# P06_PLP.net
KiCad netlist of a schematic drawn in Altium Designer
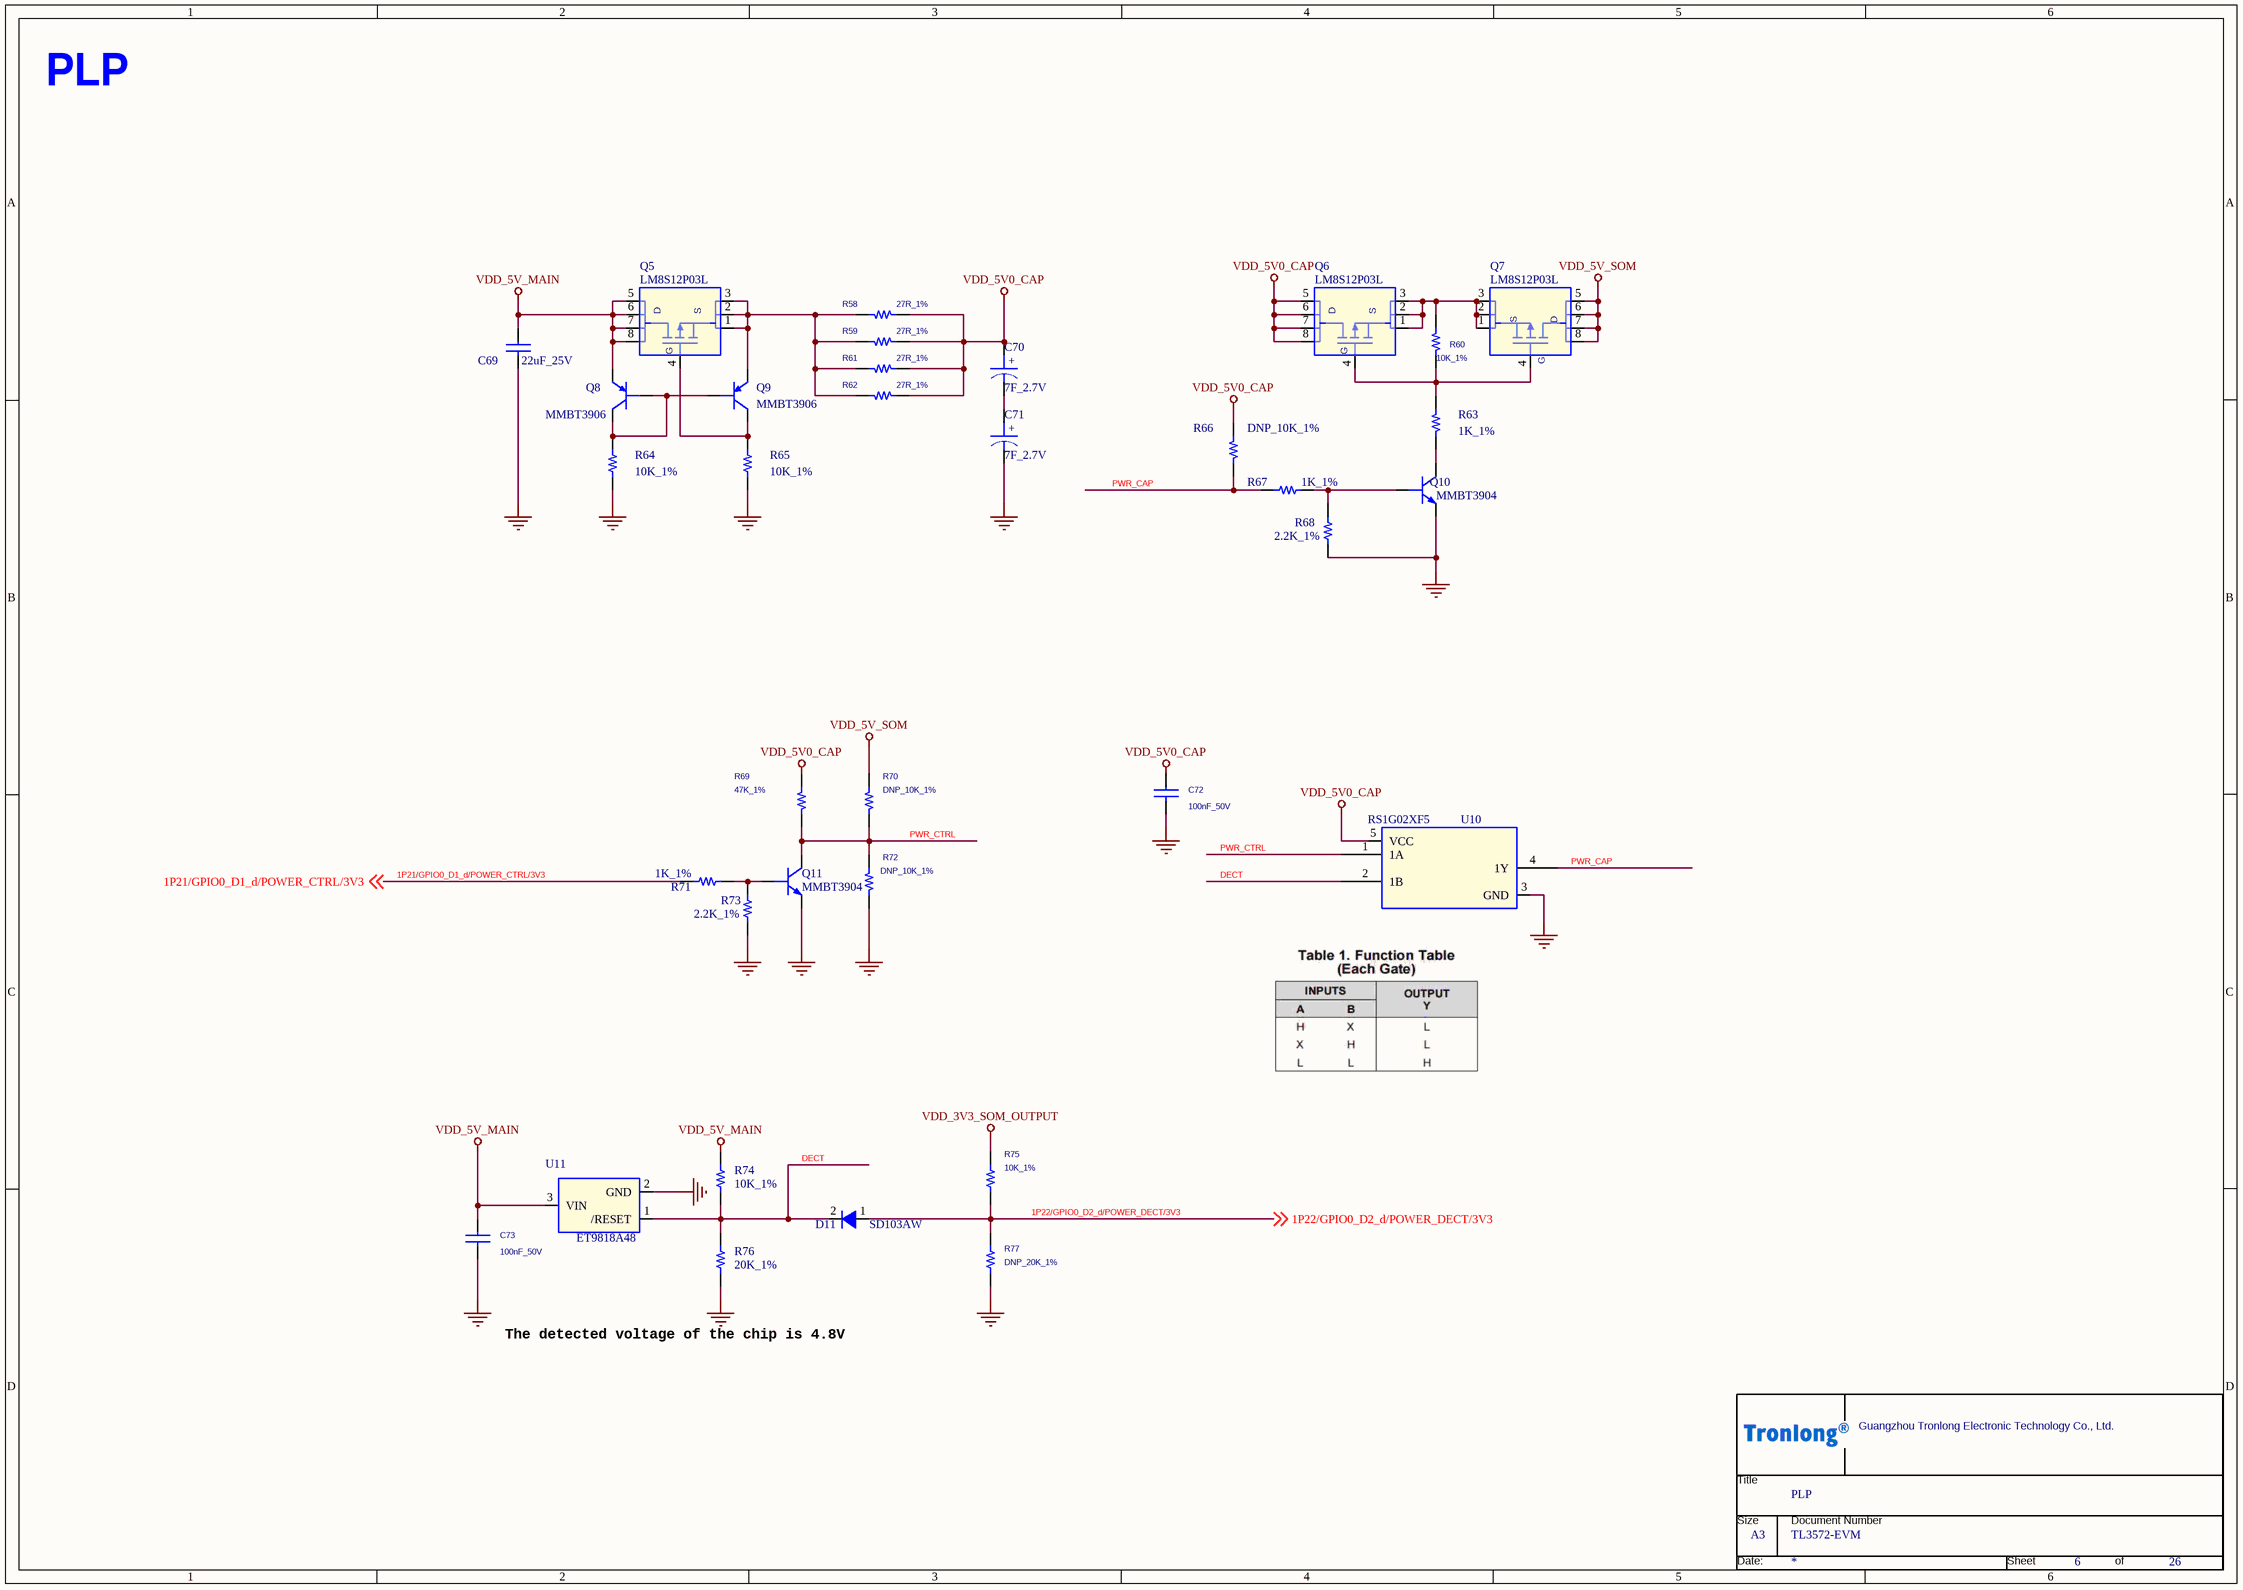
[diagram p0: P06_PLP.SchDoc]

(export (version "E")
  (design (tool "Eeschema 10.0.6"))
  (components
    (comp (ref "*")
      (value "TL_NEW")
      (fields
        (field (name "PAGE COUNT") "26")
        (field (name "PAGE NUMBER") "6")
        (field (name "PAGE SIZE") "A3")
        (field (name "ORGNAME") "Guangzhou Tronlong Electronic Technology Co., Ltd.")
        (field (name "TITLE") "PLP")
        (field (name "DOC") "TL3572-EVM")
      )
      (libsource (lib "*") (part "TL_NEW"))
    )
    (comp (ref "C69")
      (value "22uF_25V")
      (footprint "C0805")
      (description "贴片陶瓷电容,22uF,20%,25V,X5R")
      (fields
        (field (name "MANUFACTURER") "广东风华高新科技股份有限公司（FH）")
        (field (name "MANUFACTURER PARTNUMBER") "0805X226M250NT")
      )
      (libsource (lib "*") (part "CAP NP_Dup2"))
    )
    (comp (ref "C70")
      (value "7F_2.7V")
      (footprint "dcc3-5_0-10_5x20_5_0-down")
      (description "超级电容,7F,2.7V,卧式")
      (fields
        (field (name "MANUFACTURER PARTNUMBER") "HT-2R7-J705UYJ13(G211）")
        (field (name "MANUFACTURER") "锦州凯美能源有限公司（KAMCAP）")
      )
      (libsource (lib "*") (part "CAP POL_Dup1"))
    )
    (comp (ref "C71")
      (value "7F_2.7V")
      (footprint "dcc3-5_0-10_5x20_5_0-down")
      (description "超级电容,7F,2.7V,卧式")
      (fields
        (field (name "MANUFACTURER PARTNUMBER") "HT-2R7-J705UYJ13(G211）")
        (field (name "MANUFACTURER") "锦州凯美能源有限公司（KAMCAP）")
      )
      (libsource (lib "*") (part "CAP POL_Dup1"))
    )
    (comp (ref "C72")
      (value "100nF_50V")
      (footprint "C0402")
      (description "贴片陶瓷电容,100nF,10%,50V,X7R")
      (fields
        (field (name "MANUFACTURER PARTNUMBER") "0402B104K500NT")
        (field (name "MANUFACTURER") "广东风华高新科技股份有限公司（FH）")
      )
      (libsource (lib "*") (part "CAP_NP_Dup1"))
    )
    (comp (ref "C73")
      (value "100nF_50V")
      (footprint "C0402")
      (description "贴片陶瓷电容,100nF,10%,50V,X7R")
      (fields
        (field (name "MANUFACTURER PARTNUMBER") "0402B104K500NT")
        (field (name "MANUFACTURER") "广东风华高新科技股份有限公司（FH）")
      )
      (libsource (lib "*") (part "CAP_NP_Dup1"))
    )
    (comp (ref "D11")
      (value "SD103AW")
      (footprint "SOD-123_NEW")
      (description "肖特基二极管,VR=40V,IF=350mA,VF=0.37V@20mA,trr=10ns")
      (fields (field (name "TIINTPARTNUMBER") "1E0013") (field (name "MFR") "On Semiconductor"))
      (libsource (lib "*") (part "Diode200mA250V_1"))
    )
    (comp (ref "Q5")
      (value "LM8S12P03L")
      (footprint "PSOPSOP-8L")
      (description "MOSFET,P沟道,VDSS=-30V,VGSS=±20V,ID=-12A,PD=3.1W,VGS(th)=-1.5V")
      (fields (field (name "MANUFACTURER") "上海雷卯电子科技有限公司（Leiditech）"))
      (libsource (lib "") (part "WPM3021_1"))
    )
    (comp (ref "Q6")
      (value "LM8S12P03L")
      (footprint "PSOPSOP-8L")
      (description "MOSFET,P沟道,VDSS=-30V,VGSS=±20V,ID=-12A,PD=3.1W,VGS(th)=-1.5V")
      (fields (field (name "MANUFACTURER") "上海雷卯电子科技有限公司（Leiditech）"))
      (libsource (lib "") (part "WPM3021_1"))
    )
    (comp (ref "Q7")
      (value "LM8S12P03L")
      (footprint "PSOPSOP-8L")
      (description "MOSFET,P沟道,VDSS=-30V,VGSS=±20V,ID=-12A,PD=3.1W,VGS(th)=-1.5V")
      (fields (field (name "MANUFACTURER") "上海雷卯电子科技有限公司（Leiditech）"))
      (libsource (lib "*") (part "WPM3021"))
    )
    (comp (ref "Q8")
      (value "MMBT3906")
      (footprint "SOT23-3_DBZ3")
      (description "BJT,PNP,Vceo=-40V,Ic=-200mA,fT=300MHz,PD=200mW")
      (fields (field (name "MANUFACTURER") "江苏长晶科技股份有限公司（JSCJ）"))
      (libsource (lib "*") (part "MMBT3904/SOT_0"))
    )
    (comp (ref "Q9")
      (value "MMBT3906")
      (footprint "SOT23-3_DBZ3")
      (description "BJT,PNP,Vceo=-40V,Ic=-200mA,fT=300MHz,PD=200mW")
      (fields (field (name "MANUFACTURER") "江苏长晶科技股份有限公司（JSCJ）"))
      (libsource (lib "*") (part "MMBT3904/SOT_0"))
    )
    (comp (ref "Q10")
      (value "MMBT3904")
      (footprint "SOT23-3_DBZ3")
      (description "BJT,NPN,Vceo=40V,Ic=200mA,fT=300MHz,PD=200mW")
      (fields (field (name "MANUFACTURER") "江苏长晶科技股份有限公司（JSCJ）"))
      (libsource (lib "*") (part "MMBT3904/SOT"))
    )
    (comp (ref "Q11")
      (value "MMBT3904")
      (footprint "SOT23-3_DBZ3")
      (description "BJT,NPN,Vceo=40V,Ic=200mA,fT=300MHz,PD=200mW")
      (fields (field (name "MANUFACTURER") "江苏长晶科技股份有限公司（JSCJ）"))
      (libsource (lib "*") (part "MMBT3904/SOT"))
    )
    (comp (ref "R58")
      (value "27R_1%")
      (footprint "R2512")
      (description "25121WF270JT4E")
      (fields
        (field (name "MANUFACTURER") "广州创龙")
        (field (name "MANUFACTURER PARTNUMBER") "27R,±1%,R2512,≥1W")
      )
      (libsource (lib "*") (part "Resistor_Dup3"))
    )
    (comp (ref "R59")
      (value "27R_1%")
      (footprint "R2512")
      (description "25121WF270JT4E")
      (fields
        (field (name "MANUFACTURER") "广州创龙")
        (field (name "MANUFACTURER PARTNUMBER") "27R,±1%,R2512,≥1W")
      )
      (libsource (lib "*") (part "Resistor_Dup3"))
    )
    (comp (ref "R60")
      (value "10K_1%")
      (footprint "R0402")
      (description "贴片电阻,10K,±1%,1/16W")
      (fields
        (field (name "MANUFACTURER") "广东风华高新科技股份有限公司（FH）")
        (field (name "MANUFACTURER PARTNUMBER") "RC-02K1002FT")
      )
      (libsource (lib "*") (part "Resistor_Dup3"))
    )
    (comp (ref "R61")
      (value "27R_1%")
      (footprint "R2512")
      (description "25121WF270JT4E")
      (fields
        (field (name "MANUFACTURER") "广州创龙")
        (field (name "MANUFACTURER PARTNUMBER") "27R,±1%,R2512,≥1W")
      )
      (libsource (lib "*") (part "Resistor_Dup3"))
    )
    (comp (ref "R62")
      (value "27R_1%")
      (footprint "R2512")
      (description "25121WF270JT4E")
      (fields
        (field (name "MANUFACTURER") "广州创龙")
        (field (name "MANUFACTURER PARTNUMBER") "27R,±1%,R2512,≥1W")
      )
      (libsource (lib "*") (part "Resistor_Dup3"))
    )
    (comp (ref "R63")
      (value "1K_1%")
      (footprint "R0402")
      (description "贴片电阻,1K,±1%,1/16W")
      (fields
        (field (name "MANUFACTURER PARTNUMBER") "RC-02K1001FT")
        (field (name "MANUFACTURER") "广东风华高新科技股份有限公司（FH）")
      )
      (libsource (lib "*") (part "Resistor_Dup3"))
    )
    (comp (ref "R64")
      (value "10K_1%")
      (footprint "R0402")
      (description "贴片电阻,10K,±1%,1/16W")
      (fields
        (field (name "MANUFACTURER PARTNUMBER") "RC-02K1002FT")
        (field (name "MANUFACTURER") "广东风华高新科技股份有限公司（FH）")
      )
      (libsource (lib "*") (part "Resistor_Dup3"))
    )
    (comp (ref "R65")
      (value "10K_1%")
      (footprint "R0402")
      (description "贴片电阻,10K,±1%,1/16W")
      (fields
        (field (name "MANUFACTURER") "广东风华高新科技股份有限公司（FH）")
        (field (name "MANUFACTURER PARTNUMBER") "RC-02K1002FT")
      )
      (libsource (lib "*") (part "Resistor_Dup3"))
    )
    (comp (ref "R66")
      (value "DNP_10K_1%")
      (footprint "R0402")
      (description "贴片电阻,10K,±1%,1/16W")
      (fields
        (field (name "MANUFACTURER") "广东风华高新科技股份有限公司（FH）")
        (field (name "MANUFACTURER PARTNUMBER") "RC-02K1002FT")
      )
      (libsource (lib "*") (part "Resistor_Dup3"))
    )
    (comp (ref "R67")
      (value "1K_1%")
      (footprint "R0402")
      (description "贴片电阻,1K,±1%,1/16W")
      (fields
        (field (name "MANUFACTURER") "广东风华高新科技股份有限公司（FH）")
        (field (name "MANUFACTURER PARTNUMBER") "RC-02K1001FT")
      )
      (libsource (lib "*") (part "Resistor_Dup3"))
    )
    (comp (ref "R68")
      (value "2.2K_1%")
      (footprint "R0402")
      (description "贴片电阻,2.2K,±1%,1/16W")
      (fields
        (field (name "MANUFACTURER PARTNUMBER") "RC-02K2201FT")
        (field (name "MANUFACTURER") "广东风华高新科技股份有限公司（FH）")
      )
      (libsource (lib "*") (part "Resistor_Dup3"))
    )
    (comp (ref "R69")
      (value "47K_1%")
      (footprint "R0402")
      (description "贴片电阻,47K,±1%,1/16W")
      (fields
        (field (name "MANUFACTURER") "广东风华高新科技股份有限公司（FH）")
        (field (name "MANUFACTURER PARTNUMBER") "RC-02K4702FT")
      )
      (libsource (lib "*") (part "Resistor_Dup3"))
    )
    (comp (ref "R70")
      (value "DNP_10K_1%")
      (footprint "R0402")
      (description "贴片电阻,10K,±1%,1/16W")
      (fields
        (field (name "MANUFACTURER PARTNUMBER") "RC-02K1002FT")
        (field (name "MANUFACTURER") "广东风华高新科技股份有限公司（FH）")
      )
      (libsource (lib "*") (part "Resistor_Dup3"))
    )
    (comp (ref "R71")
      (value "1K_1%")
      (footprint "R0402")
      (description "贴片电阻,1K,±1%,1/16W")
      (fields
        (field (name "MANUFACTURER") "广东风华高新科技股份有限公司（FH）")
        (field (name "MANUFACTURER PARTNUMBER") "RC-02K1001FT")
      )
      (libsource (lib "*") (part "Resistor_Dup3"))
    )
    (comp (ref "R72")
      (value "DNP_10K_1%")
      (footprint "R0402")
      (description "贴片电阻,10K,±1%,1/16W")
      (fields
        (field (name "MANUFACTURER") "广东风华高新科技股份有限公司（FH）")
        (field (name "MANUFACTURER PARTNUMBER") "RC-02K1002FT")
      )
      (libsource (lib "*") (part "Resistor_Dup3"))
    )
    (comp (ref "R73")
      (value "2.2K_1%")
      (footprint "R0402")
      (description "贴片电阻,2.2K,±1%,1/16W")
      (fields
        (field (name "MANUFACTURER") "广东风华高新科技股份有限公司（FH）")
        (field (name "MANUFACTURER PARTNUMBER") "RC-02K2201FT")
      )
      (libsource (lib "*") (part "Resistor_Dup3"))
    )
    (comp (ref "R74")
      (value "10K_1%")
      (footprint "R0402")
      (description "贴片电阻,10K,±1%,1/16W")
      (fields
        (field (name "MANUFACTURER") "广东风华高新科技股份有限公司（FH）")
        (field (name "MANUFACTURER PARTNUMBER") "RC-02K1002FT")
      )
      (libsource (lib "*") (part "Resistor_Dup3"))
    )
    (comp (ref "R75")
      (value "10K_1%")
      (footprint "R0402")
      (description "贴片电阻,10K,±1%,1/16W")
      (fields
        (field (name "MANUFACTURER PARTNUMBER") "RC-02K1002FT")
        (field (name "MANUFACTURER") "广东风华高新科技股份有限公司（FH）")
      )
      (libsource (lib "*") (part "Resistor_Dup3"))
    )
    (comp (ref "R76")
      (value "20K_1%")
      (footprint "R0603")
      (description "贴片电阻,20K,±1%,1/10W")
      (fields
        (field (name "MANUFACTURER PARTNUMBER") "RS-03K2002FT")
        (field (name "MANUFACTURER") "广东风华高新科技股份有限公司（FH）")
      )
      (libsource (lib "*") (part "Resistor_Dup3"))
    )
    (comp (ref "R77")
      (value "DNP_20K_1%")
      (footprint "R0402")
      (description "贴片电阻,20K,±1%,1/16W")
      (fields
        (field (name "MANUFACTURER") "广东风华高新科技股份有限公司（FH）")
        (field (name "MANUFACTURER PARTNUMBER") "RC-02K2002FT")
      )
      (libsource (lib "*") (part "Resistor_Dup3"))
    )
    (comp (ref "U10")
      (value "RS1G02XF5")
      (footprint "SOT23-5")
      (description "1个两输入或非门")
      (fields (field (name "MANUFACTURER") "江苏润石科技有限公司（RUNIC）"))
      (libsource (lib "TL3572-EVM-A1.0-000-r-SCH-202606291501") (part "SN74LVC2G86DCUR _0"))
    )
    (comp (ref "U11")
      (value "ET9818A48")
      (footprint "sot23-3_dbz3_1")
      (description "电源监控,4.8V,阈值电压4.7V")
      (fields (field (name "MANUFACTURER") "无锡力芯微电子股份有限公司（ETEK）"))
      (libsource (lib "*") (part "WD1304E30_0"))
    )
  )
  (nets
    (net (code "1") (name "/DECT") (class "Default")
      (node (ref "D11") (pin "2") (pinfunction "Cathode_2") (pintype "passive"))
      (node (ref "R74") (pin "1") (pinfunction "1_1") (pintype "passive"))
      (node (ref "R76") (pin "2") (pinfunction "2_2") (pintype "passive"))
      (node (ref "U10") (pin "2") (pinfunction "1B_2") (pintype "passive"))
      (node (ref "U11") (pin "1") (pinfunction "/RESET_1") (pintype "power_in"))
    )
    (net (code "2") (name "/PWR_CAP") (class "Default")
      (node (ref "R66") (pin "2") (pinfunction "2_2") (pintype "passive"))
      (node (ref "R67") (pin "2") (pinfunction "2_2") (pintype "passive"))
      (node (ref "U10") (pin "4") (pinfunction "1Y_4") (pintype "passive"))
    )
    (net (code "3") (name "/PWR_CTRL") (class "Default")
      (node (ref "Q11") (pin "3") (pinfunction "C_3") (pintype "passive"))
      (node (ref "R69") (pin "2") (pinfunction "2_2") (pintype "passive"))
      (node (ref "R70") (pin "2") (pinfunction "2_2") (pintype "passive"))
      (node (ref "R72") (pin "1") (pinfunction "1_1") (pintype "passive"))
      (node (ref "U10") (pin "1") (pinfunction "1A_1") (pintype "passive"))
    )
    (net (code "4") (name "1P21{slash}GPIO0_D1_d{slash}POWER_CTRL{slash}3V3") (class "Default")
      (node (ref "R71") (pin "2") (pinfunction "2_2") (pintype "passive"))
    )
    (net (code "5") (name "1P22{slash}GPIO0_D2_d{slash}POWER_DECT{slash}3V3") (class "Default")
      (node (ref "D11") (pin "1") (pinfunction "Anode_1") (pintype "passive"))
      (node (ref "R75") (pin "2") (pinfunction "2_2") (pintype "passive"))
      (node (ref "R77") (pin "1") (pinfunction "1_1") (pintype "passive"))
    )
    (net (code "6") (name "GND") (class "Default")
      (node (ref "C69") (pin "2") (pinfunction "2_2") (pintype "passive"))
      (node (ref "C71") (pin "2") (pinfunction "2_2") (pintype "passive"))
      (node (ref "C72") (pin "2") (pinfunction "2_2") (pintype "passive"))
      (node (ref "C73") (pin "2") (pinfunction "2_2") (pintype "passive"))
      (node (ref "Q10") (pin "2") (pinfunction "E_2") (pintype "passive"))
      (node (ref "Q11") (pin "2") (pinfunction "E_2") (pintype "passive"))
      (node (ref "R64") (pin "1") (pinfunction "1_1") (pintype "passive"))
      (node (ref "R65") (pin "1") (pinfunction "1_1") (pintype "passive"))
      (node (ref "R68") (pin "2") (pinfunction "2_2") (pintype "passive"))
      (node (ref "R72") (pin "2") (pinfunction "2_2") (pintype "passive"))
      (node (ref "R73") (pin "2") (pinfunction "2_2") (pintype "passive"))
      (node (ref "R76") (pin "1") (pinfunction "1_1") (pintype "passive"))
      (node (ref "R77") (pin "2") (pinfunction "2_2") (pintype "passive"))
      (node (ref "U10") (pin "3") (pinfunction "GND_3") (pintype "power_in"))
      (node (ref "U11") (pin "2") (pinfunction "GND_2") (pintype "passive"))
    )
    (net (code "7") (name "Net-(C70-Pad2)") (class "Default")
      (node (ref "C70") (pin "2") (pinfunction "2_2") (pintype "passive"))
      (node (ref "C71") (pin "1") (pinfunction "1_1") (pintype "passive"))
    )
    (net (code "8") (name "Net-(Q5-G)") (class "Default")
      (node (ref "Q5") (pin "4") (pinfunction "G_4") (pintype "passive"))
      (node (ref "Q9") (pin "3") (pinfunction "C_3") (pintype "passive"))
      (node (ref "R65") (pin "2") (pinfunction "2_2") (pintype "passive"))
    )
    (net (code "9") (name "Net-(Q5-S1)") (class "Default")
      (node (ref "Q5") (pin "1") (pinfunction "S1_1") (pintype "passive"))
      (node (ref "Q5") (pin "2") (pinfunction "S2_2") (pintype "passive"))
      (node (ref "Q5") (pin "3") (pinfunction "S3_3") (pintype "passive"))
      (node (ref "Q9") (pin "2") (pinfunction "E_2") (pintype "passive"))
      (node (ref "R58") (pin "2") (pinfunction "2_2") (pintype "passive"))
      (node (ref "R59") (pin "2") (pinfunction "2_2") (pintype "passive"))
      (node (ref "R61") (pin "2") (pinfunction "2_2") (pintype "passive"))
      (node (ref "R62") (pin "2") (pinfunction "2_2") (pintype "passive"))
    )
    (net (code "10") (name "Net-(Q6-G)") (class "Default")
      (node (ref "Q6") (pin "4") (pinfunction "G_4") (pintype "passive"))
      (node (ref "Q7") (pin "4") (pinfunction "G_4") (pintype "passive"))
      (node (ref "R60") (pin "1") (pinfunction "1_1") (pintype "passive"))
      (node (ref "R63") (pin "2") (pinfunction "2_2") (pintype "passive"))
    )
    (net (code "11") (name "Net-(Q6-S1)") (class "Default")
      (node (ref "Q6") (pin "1") (pinfunction "S1_1") (pintype "passive"))
      (node (ref "Q6") (pin "2") (pinfunction "S2_2") (pintype "passive"))
      (node (ref "Q6") (pin "3") (pinfunction "S3_3") (pintype "passive"))
      (node (ref "Q7") (pin "1") (pinfunction "S1_1") (pintype "passive"))
      (node (ref "Q7") (pin "2") (pinfunction "S2_2") (pintype "passive"))
      (node (ref "Q7") (pin "3") (pinfunction "S3_3") (pintype "passive"))
      (node (ref "R60") (pin "2") (pinfunction "2_2") (pintype "passive"))
    )
    (net (code "12") (name "Net-(Q8-B)") (class "Default")
      (node (ref "Q8") (pin "1") (pinfunction "B_1") (pintype "passive"))
      (node (ref "Q8") (pin "3") (pinfunction "C_3") (pintype "passive"))
      (node (ref "Q9") (pin "1") (pinfunction "B_1") (pintype "passive"))
      (node (ref "R64") (pin "2") (pinfunction "2_2") (pintype "passive"))
    )
    (net (code "13") (name "Net-(Q10-B)") (class "Default")
      (node (ref "Q10") (pin "1") (pinfunction "B_1") (pintype "passive"))
      (node (ref "R67") (pin "1") (pinfunction "1_1") (pintype "passive"))
      (node (ref "R68") (pin "1") (pinfunction "1_1") (pintype "passive"))
    )
    (net (code "14") (name "Net-(Q10-C)") (class "Default")
      (node (ref "Q10") (pin "3") (pinfunction "C_3") (pintype "passive"))
      (node (ref "R63") (pin "1") (pinfunction "1_1") (pintype "passive"))
    )
    (net (code "15") (name "Net-(Q11-B)") (class "Default")
      (node (ref "Q11") (pin "1") (pinfunction "B_1") (pintype "passive"))
      (node (ref "R71") (pin "1") (pinfunction "1_1") (pintype "passive"))
      (node (ref "R73") (pin "1") (pinfunction "1_1") (pintype "passive"))
    )
    (net (code "16") (name "VDD_3V3_SOM_OUTPUT") (class "Default")
      (node (ref "R75") (pin "1") (pinfunction "1_1") (pintype "passive"))
    )
    (net (code "17") (name "VDD_5V0_CAP") (class "Default")
      (node (ref "C70") (pin "1") (pinfunction "1_1") (pintype "passive"))
      (node (ref "C72") (pin "1") (pinfunction "1_1") (pintype "passive"))
      (node (ref "Q6") (pin "5") (pinfunction "D1_5") (pintype "passive"))
      (node (ref "Q6") (pin "6") (pinfunction "D2_6") (pintype "passive"))
      (node (ref "Q6") (pin "7") (pinfunction "D3_7") (pintype "passive"))
      (node (ref "Q6") (pin "8") (pinfunction "D4_8") (pintype "passive"))
      (node (ref "R58") (pin "1") (pinfunction "1_1") (pintype "passive"))
      (node (ref "R59") (pin "1") (pinfunction "1_1") (pintype "passive"))
      (node (ref "R61") (pin "1") (pinfunction "1_1") (pintype "passive"))
      (node (ref "R62") (pin "1") (pinfunction "1_1") (pintype "passive"))
      (node (ref "R66") (pin "1") (pinfunction "1_1") (pintype "passive"))
      (node (ref "R69") (pin "1") (pinfunction "1_1") (pintype "passive"))
      (node (ref "U10") (pin "5") (pinfunction "VCC_5") (pintype "power_in"))
    )
    (net (code "18") (name "VDD_5V_MAIN") (class "Default")
      (node (ref "C69") (pin "1") (pinfunction "1_1") (pintype "passive"))
      (node (ref "C73") (pin "1") (pinfunction "1_1") (pintype "passive"))
      (node (ref "Q5") (pin "5") (pinfunction "D1_5") (pintype "passive"))
      (node (ref "Q5") (pin "6") (pinfunction "D2_6") (pintype "passive"))
      (node (ref "Q5") (pin "7") (pinfunction "D3_7") (pintype "passive"))
      (node (ref "Q5") (pin "8") (pinfunction "D4_8") (pintype "passive"))
      (node (ref "Q8") (pin "2") (pinfunction "E_2") (pintype "passive"))
      (node (ref "R74") (pin "2") (pinfunction "2_2") (pintype "passive"))
      (node (ref "U11") (pin "3") (pinfunction "VIN_3") (pintype "passive"))
    )
    (net (code "19") (name "VDD_5V_SOM") (class "Default")
      (node (ref "Q7") (pin "5") (pinfunction "D1_5") (pintype "passive"))
      (node (ref "Q7") (pin "6") (pinfunction "D2_6") (pintype "passive"))
      (node (ref "Q7") (pin "7") (pinfunction "D3_7") (pintype "passive"))
      (node (ref "Q7") (pin "8") (pinfunction "D4_8") (pintype "passive"))
      (node (ref "R70") (pin "1") (pinfunction "1_1") (pintype "passive"))
    )
  )
)
